# POWER.net
KiCad netlist of a schematic drawn in Altium Designer
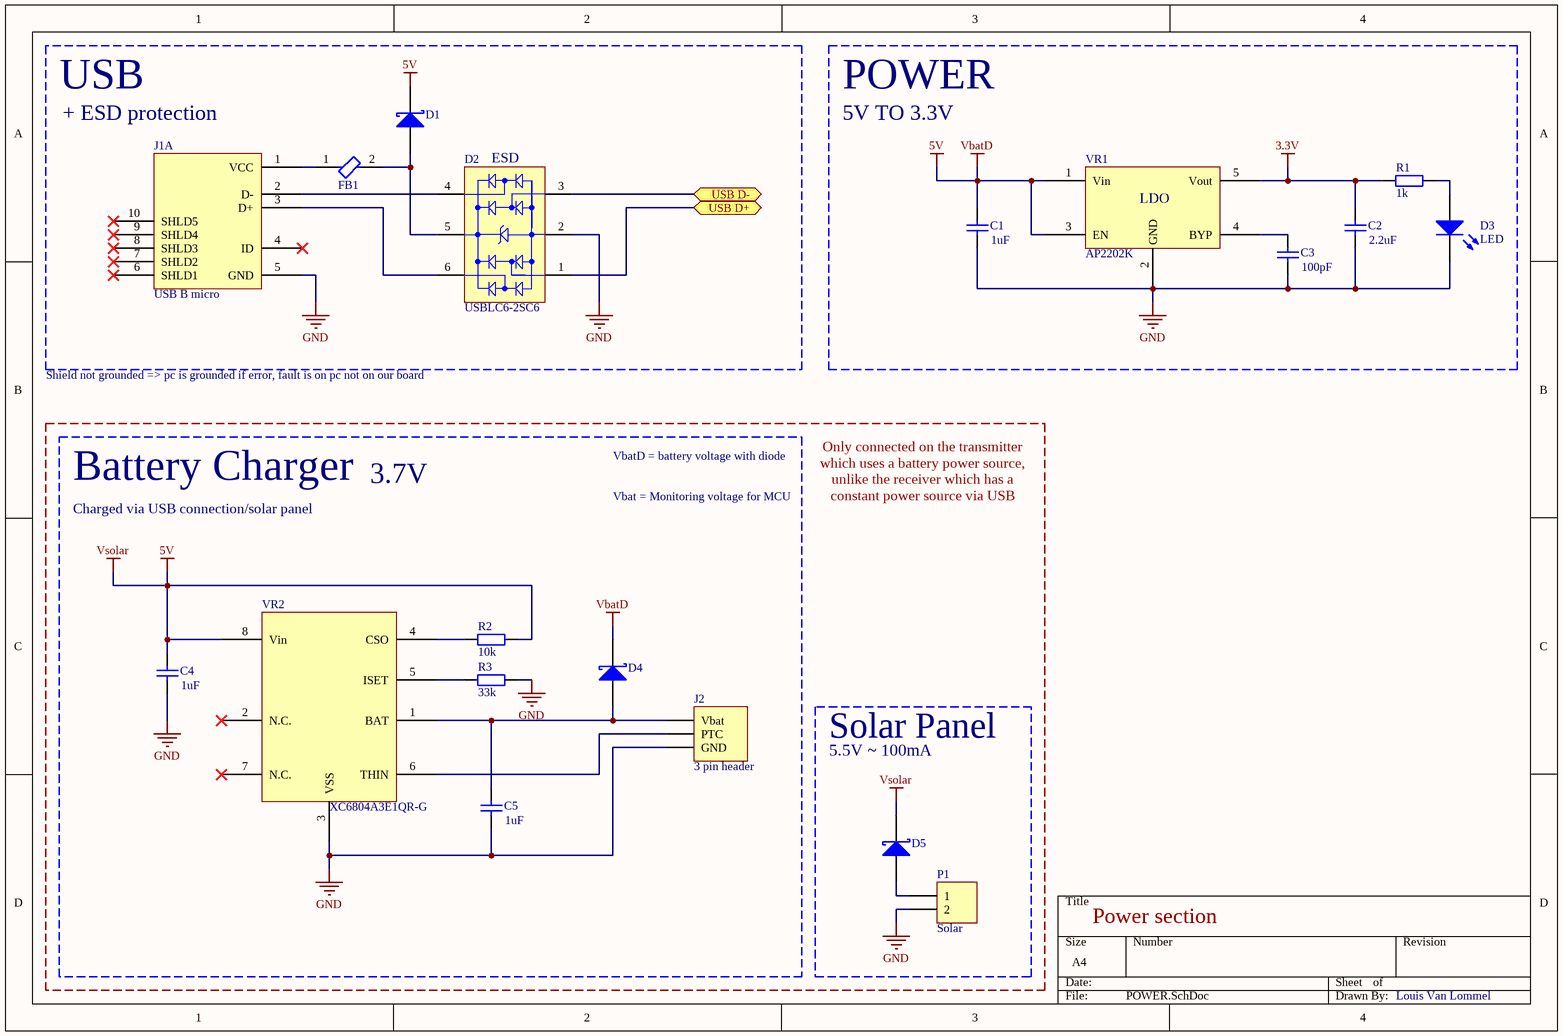
[diagram p0: POWER.SchDoc]

(export (version "E")
  (design (tool "Eeschema 10.0.6"))
  (components
    (comp (ref "C1")
      (value "1uF")
      (footprint "CAP_0603")
      (description "Capacitor")
      (fields (field (name "PUBLISHER") "Altium Limited"))
      (libsource (lib "Miscellaneous Devices") (part "Cap"))
    )
    (comp (ref "C2")
      (value "2.2uF")
      (footprint "CAP_0603")
      (description "Capacitor")
      (fields (field (name "PUBLISHER") "Altium Limited"))
      (libsource (lib "Miscellaneous Devices") (part "Cap"))
    )
    (comp (ref "C3")
      (value "100pF")
      (footprint "CAP_0603")
      (description "Capacitor")
      (fields (field (name "PUBLISHER") "Altium Limited"))
      (libsource (lib "Miscellaneous Devices") (part "Cap"))
    )
    (comp (ref "C4")
      (value "1uF")
      (footprint "CAP_0603")
      (description "Capacitor")
      (fields (field (name "PUBLISHER") "Altium Limited"))
      (libsource (lib "Miscellaneous Devices") (part "Cap"))
    )
    (comp (ref "C5")
      (value "1uF")
      (footprint "CAP_0603")
      (description "Capacitor")
      (fields (field (name "PUBLISHER") "Altium Limited"))
      (libsource (lib "Miscellaneous Devices") (part "Cap"))
    )
    (comp (ref "D1")
      (value "~")
      (footprint "SOT-23_L")
      (description "Silicon RF Schottky Diode for Mixer Applications in the VHF/UHF Range")
      (fields (field (name "PUBLISHER") "Altium Limited"))
      (libsource (lib "Miscellaneous Devices") (part "Diode BAT17"))
    )
    (comp (ref "D2")
      (value "USBLC6-2SC6")
      (footprint "STM-SOT23-6L_V")
      (description "Very low capacitance ESD protection, 3.5 pF, -40 to 125 degC, 6-Pin SOT23, RoHS, Tape and Reel")
      (fields (field (name "MANUFACTURER") "STMicroelectronics"))
      (libsource (lib "Altium Content Vault") (part "STM-USB_DVI_HDMIULC6-4SC6X-SOT23-6L"))
    )
    (comp (ref "D3")
      (value "LED")
      (footprint "LED_0603")
      (description "Typical RED, GREEN, YELLOW, AMBER GaAs LED")
      (fields (field (name "PUBLISHER") "Altium Limited"))
      (libsource (lib "Miscellaneous Devices") (part "LED2"))
    )
    (comp (ref "D4")
      (value "~")
      (footprint "SOT-23_L")
      (description "Silicon RF Schottky Diode for Mixer Applications in the VHF/UHF Range")
      (fields (field (name "PUBLISHER") "Altium Limited"))
      (libsource (lib "Miscellaneous Devices") (part "Diode BAT17"))
    )
    (comp (ref "D5")
      (value "~")
      (footprint "SOT-23_L")
      (description "Silicon RF Schottky Diode for Mixer Applications in the VHF/UHF Range")
      (fields (field (name "PUBLISHER") "Altium Limited"))
      (libsource (lib "Miscellaneous Devices") (part "Diode BAT17"))
    )
    (comp (ref "FB1")
      (value "BLM18PG121SN1D")
      (footprint "FP-BLM18-0_15-t0_8-IPC_A")
      (description "Chip Ferrite Bead, 0603, 120Ω @ 100MHz, 0.05Ω, 25%, 2A")
      (fields (field (name "TOLERANCE") "25%"))
      (libsource (lib "Altium Content Vault") (part "5f30dd21d616792df468990f7003faa"))
    )
    (comp (ref "J1")
      (value "USB B micro")
      (footprint "USB Micro B")
      (libsource (lib "AP2112") (part "USB micro B"))
    )
    (comp (ref "J2")
      (value "3 pin header")
      (footprint "Header_3")
      (libsource (lib "AP2112") (part "Header_3"))
    )
    (comp (ref "P1")
      (value "Solar")
      (footprint "HDR1X2")
      (description "Header, 2-Pin, Right Angle")
      (fields (field (name "PUBLISHER") "Altium Limited"))
      (libsource (lib "Miscellaneous Connectors") (part "Header 2H"))
    )
    (comp (ref "R1")
      (value "1k")
      (footprint "RES_0603")
      (description "Resistor")
      (fields (field (name "PUBLISHER") "Altium Limited"))
      (libsource (lib "Miscellaneous Devices") (part "Res2"))
    )
    (comp (ref "R2")
      (value "10k")
      (footprint "RES_0603")
      (description "Resistor")
      (fields (field (name "PUBLISHER") "Altium Limited"))
      (libsource (lib "Miscellaneous Devices") (part "Res2"))
    )
    (comp (ref "R3")
      (value "33k")
      (footprint "RES_0603")
      (fields (field (name "PUBLISHER") "Altium Limited"))
      (libsource (lib "Miscellaneous Devices") (part "Res2"))
    )
    (comp (ref "VR1")
      (value "AP2202K")
      (footprint "SOT23-5")
      (description "AP2112K-3.3TRG1 ¦ 3.3V LDO ¦ 2.5V — 13.2V")
      (libsource (lib "AP2112") (part "AP2202K-3.3TRG1"))
    )
    (comp (ref "VR2")
      (value "XC6804A3E1QR-G")
      (footprint "SOP127P600-8N")
      (libsource (lib "AP2112") (part "XC6804A3E1QR-G"))
    )
  )
  (nets
    (net (code "1") (name "/USB D+") (class "Default")
      (node (ref "D2") (pin "1") (pinfunction "I/O_1_1") (pintype "passive"))
    )
    (net (code "2") (name "/USB D-") (class "Default")
      (node (ref "D2") (pin "3") (pinfunction "I/O_2_3") (pintype "passive"))
    )
    (net (code "3") (name "3.3V") (class "Default")
      (node (ref "C2") (pin "2") (pinfunction "2_2") (pintype "passive"))
      (node (ref "R1") (pin "2") (pinfunction "2_2") (pintype "passive"))
      (node (ref "VR1") (pin "5") (pinfunction "Vout_5") (pintype "passive"))
    )
    (net (code "4") (name "5V") (class "Default")
      (node (ref "C1") (pin "2") (pinfunction "2_2") (pintype "passive"))
      (node (ref "C4") (pin "2") (pinfunction "2_2") (pintype "passive"))
      (node (ref "D1") (pin "3") (pinfunction "K_3") (pintype "passive"))
      (node (ref "D4") (pin "3") (pinfunction "K_3") (pintype "passive"))
      (node (ref "D5") (pin "3") (pinfunction "K_3") (pintype "passive"))
      (node (ref "R2") (pin "1") (pinfunction "1_1") (pintype "passive"))
      (node (ref "VR1") (pin "1") (pinfunction "Vin_1") (pintype "passive"))
      (node (ref "VR1") (pin "3") (pinfunction "EN_3") (pintype "passive"))
      (node (ref "VR2") (pin "8") (pinfunction "Vin_8") (pintype "passive"))
    )
    (net (code "5") (name "GND") (class "Default")
      (node (ref "C1") (pin "1") (pinfunction "1_1") (pintype "passive"))
      (node (ref "C2") (pin "1") (pinfunction "1_1") (pintype "passive"))
      (node (ref "C3") (pin "1") (pinfunction "1_1") (pintype "passive"))
      (node (ref "C4") (pin "1") (pinfunction "1_1") (pintype "passive"))
      (node (ref "C5") (pin "1") (pinfunction "1_1") (pintype "passive"))
      (node (ref "D2") (pin "2") (pinfunction "GND_2") (pintype "passive"))
      (node (ref "D3") (pin "2") (pinfunction "K_2") (pintype "passive"))
      (node (ref "J1") (pin "5") (pinfunction "GND_5") (pintype "passive"))
      (node (ref "J2") (pin "3") (pinfunction "GND_3") (pintype "passive"))
      (node (ref "P1") (pin "2") (pinfunction "2_2") (pintype "passive"))
      (node (ref "R3") (pin "1") (pinfunction "1_1") (pintype "passive"))
      (node (ref "VR1") (pin "2") (pinfunction "GND_2") (pintype "passive"))
      (node (ref "VR2") (pin "3") (pinfunction "VSS_3") (pintype "passive"))
    )
    (net (code "6") (name "Net-(D1-A)") (class "Default")
      (node (ref "D1") (pin "1") (pinfunction "A_1") (pintype "passive"))
      (node (ref "D2") (pin "5") (pinfunction "VBUS_5") (pintype "passive"))
      (node (ref "FB1") (pin "2") (pinfunction "2_2") (pintype "passive"))
    )
    (net (code "7") (name "Net-(D2-I{slash}O_3)") (class "Default")
      (node (ref "D2") (pin "4") (pinfunction "I/O_3_4") (pintype "passive"))
      (node (ref "J1") (pin "2") (pinfunction "D-_2") (pintype "passive"))
    )
    (net (code "8") (name "Net-(D2-I{slash}O_4)") (class "Default")
      (node (ref "D2") (pin "6") (pinfunction "I/O_4_6") (pintype "passive"))
      (node (ref "J1") (pin "3") (pinfunction "D+_3") (pintype "passive"))
    )
    (net (code "9") (name "Net-(D3-A)") (class "Default")
      (node (ref "D3") (pin "1") (pinfunction "A_1") (pintype "passive"))
      (node (ref "R1") (pin "1") (pinfunction "1_1") (pintype "passive"))
    )
    (net (code "10") (name "Net-(D4-A)") (class "Default")
      (node (ref "C5") (pin "2") (pinfunction "2_2") (pintype "passive"))
      (node (ref "D4") (pin "1") (pinfunction "A_1") (pintype "passive"))
      (node (ref "J2") (pin "1") (pinfunction "Vbat_1") (pintype "passive"))
      (node (ref "VR2") (pin "1") (pinfunction "BAT_1") (pintype "passive"))
    )
    (net (code "11") (name "Net-(D5-A)") (class "Default")
      (node (ref "D5") (pin "1") (pinfunction "A_1") (pintype "passive"))
      (node (ref "P1") (pin "1") (pinfunction "1_1") (pintype "passive"))
    )
    (net (code "12") (name "Net-(J1-VCC)") (class "Default")
      (node (ref "FB1") (pin "1") (pinfunction "1_1") (pintype "passive"))
      (node (ref "J1") (pin "1") (pinfunction "VCC_1") (pintype "passive"))
    )
    (net (code "13") (name "Net-(J2-PTC)") (class "Default")
      (node (ref "J2") (pin "2") (pinfunction "PTC_2") (pintype "passive"))
      (node (ref "VR2") (pin "6") (pinfunction "THIN_6") (pintype "passive"))
    )
    (net (code "14") (name "Net-(VR1-BYP)") (class "Default")
      (node (ref "C3") (pin "2") (pinfunction "2_2") (pintype "passive"))
      (node (ref "VR1") (pin "4") (pinfunction "BYP_4") (pintype "passive"))
    )
    (net (code "15") (name "Net-(VR2-CSO)") (class "Default")
      (node (ref "R2") (pin "2") (pinfunction "2_2") (pintype "passive"))
      (node (ref "VR2") (pin "4") (pinfunction "CSO_4") (pintype "passive"))
    )
    (net (code "16") (name "Net-(VR2-ISET)") (class "Default")
      (node (ref "R3") (pin "2") (pinfunction "2_2") (pintype "passive"))
      (node (ref "VR2") (pin "5") (pinfunction "ISET_5") (pintype "passive"))
    )
    (net (code "17") (name "unconnected-(J1-ID-Pad4)") (class "Default")
      (node (ref "J1") (pin "4") (pinfunction "ID_4") (pintype "passive+no_connect"))
    )
    (net (code "18") (name "unconnected-(J1-SHLD1-Pad6)") (class "Default")
      (node (ref "J1") (pin "6") (pinfunction "SHLD1_6") (pintype "passive+no_connect"))
    )
    (net (code "19") (name "unconnected-(J1-SHLD2-Pad7)") (class "Default")
      (node (ref "J1") (pin "7") (pinfunction "SHLD2_7") (pintype "passive+no_connect"))
    )
    (net (code "20") (name "unconnected-(J1-SHLD3-Pad8)") (class "Default")
      (node (ref "J1") (pin "8") (pinfunction "SHLD3_8") (pintype "passive+no_connect"))
    )
    (net (code "21") (name "unconnected-(J1-SHLD4-Pad9)") (class "Default")
      (node (ref "J1") (pin "9") (pinfunction "SHLD4_9") (pintype "passive+no_connect"))
    )
    (net (code "22") (name "unconnected-(J1-SHLD5-Pad10)") (class "Default")
      (node (ref "J1") (pin "10") (pinfunction "SHLD5_10") (pintype "passive+no_connect"))
    )
    (net (code "23") (name "unconnected-(VR2-N.C.-Pad2)") (class "Default")
      (node (ref "VR2") (pin "2") (pinfunction "N.C._2") (pintype "passive+no_connect"))
    )
    (net (code "24") (name "unconnected-(VR2-N.C.-Pad7)") (class "Default")
      (node (ref "VR2") (pin "7") (pinfunction "N.C._7") (pintype "passive+no_connect"))
    )
  )
)
